# mainboard.net
KiCad netlist of a schematic drawn in EAGLE
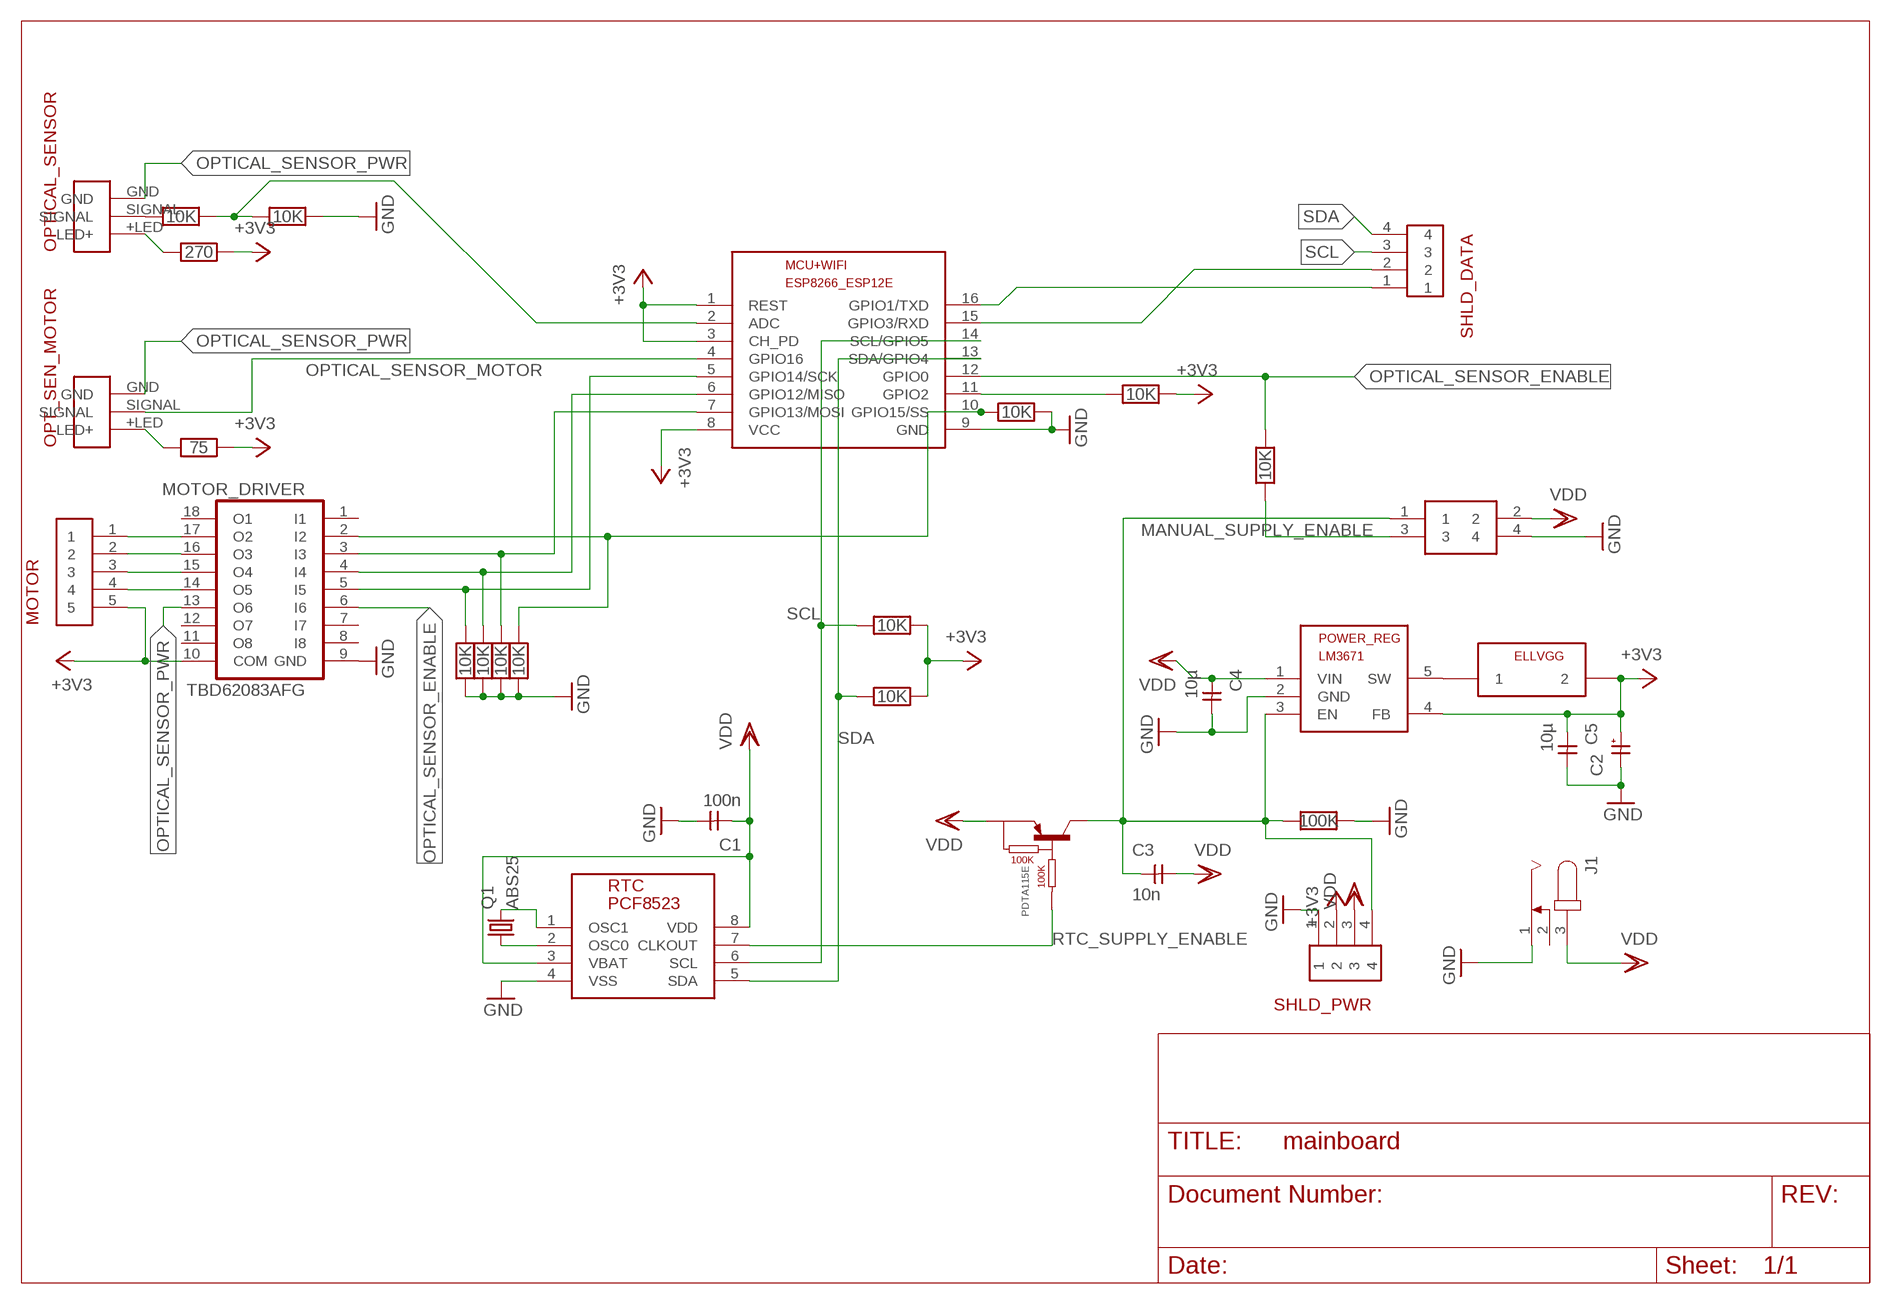
[diagram p0: schematic, sheet 1]

(export (version "E")
  (design (tool "Eeschema 10.0.6"))
  (components
    (comp (ref "C1")
      (value "100n")
      (footprint "eagle-import:SMD_RC_1206")
      (libsource (lib "eagle-import") (part "CSMD_1206"))
    )
    (comp (ref "C2")
      (value "C_POLSMD_M6.3")
      (footprint "eagle-import:C_M6.3")
      (libsource (lib "eagle-import") (part "C_POLSMD_M6.3"))
    )
    (comp (ref "C3")
      (value "10n")
      (footprint "eagle-import:SMD_RC_1206")
      (libsource (lib "eagle-import") (part "CSMD_1206"))
    )
    (comp (ref "C4")
      (value "10µ")
      (footprint "eagle-import:SMD_RC_1206")
      (libsource (lib "eagle-import") (part "CSMD_1206"))
    )
    (comp (ref "C5")
      (value "10µ")
      (footprint "eagle-import:SMD_RC_1206")
      (libsource (lib "eagle-import") (part "CSMD_1206"))
    )
    (comp (ref "DIL_SWITCH")
      (value "HEADER_2X2")
      (footprint "eagle-import:HEADER_2X2")
      (libsource (lib "eagle-import") (part "HEADER_2X2"))
    )
    (comp (ref "J1")
      (value "JACK-PLUG0")
      (footprint "eagle-import:SPC4077")
      (libsource (lib "eagle-import") (part "JACK-PLUG0"))
    )
    (comp (ref "L1")
      (value "ELLVGG")
      (footprint "eagle-import:ELLVGG")
      (libsource (lib "eagle-import") (part "ELLVGG"))
    )
    (comp (ref "MCU+WIFI")
      (value "ESP8266-12EESP8266-ESP12E")
      (footprint "eagle-import:ESP8266-ESP12E")
      (libsource (lib "eagle-import") (part "ESP8266-12EESP8266-ESP12E"))
    )
    (comp (ref "MOTOR")
      (value "B5B-XH-A")
      (footprint "eagle-import:B5B-XH-A")
      (libsource (lib "eagle-import") (part "B5B-XH-A"))
    )
    (comp (ref "MOTOR_DRIVER")
      (value "TBD62083AFG")
      (footprint "eagle-import:SO18")
      (libsource (lib "eagle-import") (part "TBD62083AFG"))
    )
    (comp (ref "OPTICAL_SENSOR")
      (value "ENDSTOP")
      (footprint "eagle-import:ENDSTOP")
      (libsource (lib "eagle-import") (part "ENDSTOP"))
    )
    (comp (ref "OPT_SEN_MOTOR")
      (value "ENDSTOP")
      (footprint "eagle-import:ENDSTOP")
      (libsource (lib "eagle-import") (part "ENDSTOP"))
    )
    (comp (ref "POWER_REG")
      (value "LM3671NO_EXTRA_PAD")
      (footprint "eagle-import:SOT23-5L-SIMPLE")
      (libsource (lib "eagle-import") (part "LM3671NO_EXTRA_PAD"))
    )
    (comp (ref "Q1")
      (value "ABS25")
      (footprint "eagle-import:ABS25")
      (libsource (lib "eagle-import") (part "ABS25"))
    )
    (comp (ref "R1")
      (value "270")
      (footprint "eagle-import:SMD_RC_1206")
      (libsource (lib "eagle-import") (part "RSMD_1206"))
    )
    (comp (ref "R2")
      (value "10K")
      (footprint "eagle-import:SMD_RC_1206")
      (libsource (lib "eagle-import") (part "RSMD_1206"))
    )
    (comp (ref "R3")
      (value "10K")
      (footprint "eagle-import:SMD_RC_1206")
      (libsource (lib "eagle-import") (part "RSMD_1206"))
    )
    (comp (ref "R4")
      (value "100K")
      (footprint "eagle-import:SMD_RC_1206")
      (libsource (lib "eagle-import") (part "RSMD_1206"))
    )
    (comp (ref "R5")
      (value "10K")
      (footprint "eagle-import:SMD_RC_1206")
      (libsource (lib "eagle-import") (part "RSMD_1206"))
    )
    (comp (ref "R6")
      (value "10K")
      (footprint "eagle-import:SMD_RC_1206")
      (libsource (lib "eagle-import") (part "RSMD_1206"))
    )
    (comp (ref "R7")
      (value "10K")
      (footprint "eagle-import:SMD_RC_1206")
      (libsource (lib "eagle-import") (part "RSMD_1206"))
    )
    (comp (ref "R8")
      (value "10K")
      (footprint "eagle-import:SMD_RC_1206")
      (libsource (lib "eagle-import") (part "RSMD_1206"))
    )
    (comp (ref "R9")
      (value "10K")
      (footprint "eagle-import:SMD_RC_1206")
      (libsource (lib "eagle-import") (part "RSMD_1206"))
    )
    (comp (ref "R10")
      (value "10K")
      (footprint "eagle-import:SMD_RC_1206")
      (libsource (lib "eagle-import") (part "RSMD_1206"))
    )
    (comp (ref "R11")
      (value "10K")
      (footprint "eagle-import:SMD_RC_1206")
      (libsource (lib "eagle-import") (part "RSMD_1206"))
    )
    (comp (ref "R12")
      (value "10K")
      (footprint "eagle-import:SMD_RC_1206")
      (libsource (lib "eagle-import") (part "RSMD_1206"))
    )
    (comp (ref "R13")
      (value "10K")
      (footprint "eagle-import:SMD_RC_1206")
      (libsource (lib "eagle-import") (part "RSMD_1206"))
    )
    (comp (ref "R14")
      (value "75")
      (footprint "eagle-import:SMD_RC_1206")
      (libsource (lib "eagle-import") (part "RSMD_1206"))
    )
    (comp (ref "RTC")
      (value "PCF8523TS")
      (footprint "eagle-import:SO8")
      (libsource (lib "eagle-import") (part "PCF8523TS"))
    )
    (comp (ref "SHLD_DATA")
      (value "HEADER_1X4")
      (footprint "eagle-import:HEADER_1X4")
      (libsource (lib "eagle-import") (part "HEADER_1X4"))
    )
    (comp (ref "SHLD_PWR")
      (value "HEADER_1X4")
      (footprint "eagle-import:HEADER_1X4")
      (libsource (lib "eagle-import") (part "HEADER_1X4"))
    )
    (comp (ref "T1")
      (value "PDTA115ET")
      (footprint "eagle-import:SOT23")
      (libsource (lib "eagle-import") (part "PDTA115ET"))
    )
  )
  (nets
    (net (code "1") (name "+3V3") (class "Default")
      (node (ref "C2") (pin "+") (pinfunction "+_+") (pintype "passive"))
      (node (ref "C5") (pin "P$1") (pinfunction "1_P$1") (pintype "passive"))
      (node (ref "L1") (pin "P$2") (pinfunction "2_P$2") (pintype "bidirectional"))
      (node (ref "MCU+WIFI") (pin "1") (pinfunction "REST_1") (pintype "bidirectional"))
      (node (ref "MCU+WIFI") (pin "3") (pinfunction "CH_PD_3") (pintype "bidirectional"))
      (node (ref "MCU+WIFI") (pin "8") (pinfunction "VCC_8") (pintype "bidirectional"))
      (node (ref "MOTOR") (pin "5") (pinfunction "5_5") (pintype "passive"))
      (node (ref "MOTOR_DRIVER") (pin "10") (pinfunction "COM_10") (pintype "passive"))
      (node (ref "POWER_REG") (pin "4") (pinfunction "FB_4") (pintype "bidirectional"))
      (node (ref "R1") (pin "P$2") (pinfunction "P$2_P$2") (pintype "passive"))
      (node (ref "R10") (pin "P$2") (pinfunction "P$2_P$2") (pintype "passive"))
      (node (ref "R11") (pin "P$2") (pinfunction "P$2_P$2") (pintype "passive"))
      (node (ref "R14") (pin "P$2") (pinfunction "P$2_P$2") (pintype "passive"))
      (node (ref "R9") (pin "P$2") (pinfunction "P$2_P$2") (pintype "passive"))
      (node (ref "SHLD_PWR") (pin "2") (pinfunction "2_2") (pintype "passive"))
    )
    (net (code "2") (name "/MANUAL_SUPPLY_ENABLE") (class "Default")
      (node (ref "C3") (pin "P$1") (pinfunction "1_P$1") (pintype "passive"))
      (node (ref "DIL_SWITCH") (pin "1") (pinfunction "1_1") (pintype "bidirectional"))
      (node (ref "POWER_REG") (pin "3") (pinfunction "EN_3") (pintype "bidirectional"))
      (node (ref "R4") (pin "P$2") (pinfunction "P$2_P$2") (pintype "passive"))
      (node (ref "SHLD_PWR") (pin "4") (pinfunction "4_4") (pintype "passive"))
      (node (ref "T1") (pin "3") (pinfunction "C_3") (pintype "passive"))
    )
    (net (code "3") (name "/OPTICAL_SENSOR_MOTOR") (class "Default")
      (node (ref "MCU+WIFI") (pin "4") (pinfunction "GPIO16_4") (pintype "bidirectional"))
      (node (ref "OPT_SEN_MOTOR") (pin "SIGNAL") (pinfunction "SIGNAL_SIGNAL") (pintype "passive"))
    )
    (net (code "4") (name "/RTC_SUPPLY_ENABLE") (class "Default")
      (node (ref "RTC") (pin "7") (pinfunction "CLKOUT_7") (pintype "output"))
      (node (ref "T1") (pin "1") (pinfunction "B_1") (pintype "passive"))
    )
    (net (code "5") (name "GND") (class "Default")
      (node (ref "C1") (pin "P$2") (pinfunction "2_P$2") (pintype "passive"))
      (node (ref "C2") (pin "GND") (pinfunction "GND_GND") (pintype "passive"))
      (node (ref "C4") (pin "P$2") (pinfunction "2_P$2") (pintype "passive"))
      (node (ref "C5") (pin "P$2") (pinfunction "2_P$2") (pintype "passive"))
      (node (ref "DIL_SWITCH") (pin "4") (pinfunction "4_4") (pintype "bidirectional"))
      (node (ref "J1") (pin "1") (pinfunction "1_1") (pintype "passive"))
      (node (ref "MCU+WIFI") (pin "9") (pinfunction "GND_9") (pintype "bidirectional"))
      (node (ref "MOTOR_DRIVER") (pin "9") (pinfunction "GND_9") (pintype "power_in"))
      (node (ref "POWER_REG") (pin "2") (pinfunction "GND_2") (pintype "bidirectional"))
      (node (ref "R12") (pin "P$1") (pinfunction "P$1_P$1") (pintype "passive"))
      (node (ref "R13") (pin "P$1") (pinfunction "P$1_P$1") (pintype "passive"))
      (node (ref "R3") (pin "P$2") (pinfunction "P$2_P$2") (pintype "passive"))
      (node (ref "R4") (pin "P$1") (pinfunction "P$1_P$1") (pintype "passive"))
      (node (ref "R5") (pin "P$1") (pinfunction "P$1_P$1") (pintype "passive"))
      (node (ref "R6") (pin "P$1") (pinfunction "P$1_P$1") (pintype "passive"))
      (node (ref "R7") (pin "P$2") (pinfunction "P$2_P$2") (pintype "passive"))
      (node (ref "RTC") (pin "4") (pinfunction "VSS_4") (pintype "power_in"))
      (node (ref "SHLD_PWR") (pin "1") (pinfunction "1_1") (pintype "passive"))
    )
    (net (code "6") (name "Net-(DIL_SWITCH-Pad3)") (class "Default")
      (node (ref "DIL_SWITCH") (pin "3") (pinfunction "3_3") (pintype "bidirectional"))
      (node (ref "R8") (pin "P$2") (pinfunction "P$2_P$2") (pintype "passive"))
    )
    (net (code "7") (name "Net-(L1-1)") (class "Default")
      (node (ref "L1") (pin "P$1") (pinfunction "1_P$1") (pintype "bidirectional"))
      (node (ref "POWER_REG") (pin "5") (pinfunction "SW_5") (pintype "bidirectional"))
    )
    (net (code "8") (name "Net-(MCU+WIFI-ADC)") (class "Default")
      (node (ref "MCU+WIFI") (pin "2") (pinfunction "ADC_2") (pintype "bidirectional"))
      (node (ref "R2") (pin "P$2") (pinfunction "P$2_P$2") (pintype "passive"))
      (node (ref "R3") (pin "P$1") (pinfunction "P$1_P$1") (pintype "passive"))
    )
    (net (code "9") (name "Net-(MCU+WIFI-GPIO1{slash}TXD)") (class "Default")
      (node (ref "MCU+WIFI") (pin "16") (pinfunction "GPIO1/TXD_16") (pintype "bidirectional"))
      (node (ref "SHLD_DATA") (pin "1") (pinfunction "1_1") (pintype "passive"))
    )
    (net (code "10") (name "Net-(MCU+WIFI-GPIO2)") (class "Default")
      (node (ref "MCU+WIFI") (pin "11") (pinfunction "GPIO2_11") (pintype "bidirectional"))
      (node (ref "R11") (pin "P$1") (pinfunction "P$1_P$1") (pintype "passive"))
    )
    (net (code "11") (name "Net-(MCU+WIFI-GPIO3{slash}RXD)") (class "Default")
      (node (ref "MCU+WIFI") (pin "15") (pinfunction "GPIO3/RXD_15") (pintype "bidirectional"))
      (node (ref "SHLD_DATA") (pin "2") (pinfunction "2_2") (pintype "passive"))
    )
    (net (code "12") (name "Net-(MCU+WIFI-GPIO12{slash}MISO)") (class "Default")
      (node (ref "MCU+WIFI") (pin "6") (pinfunction "GPIO12/MISO_6") (pintype "bidirectional"))
      (node (ref "MOTOR_DRIVER") (pin "4") (pinfunction "I4_4") (pintype "input"))
      (node (ref "R6") (pin "P$2") (pinfunction "P$2_P$2") (pintype "passive"))
    )
    (net (code "13") (name "Net-(MCU+WIFI-GPIO13{slash}MOSI)") (class "Default")
      (node (ref "MCU+WIFI") (pin "7") (pinfunction "GPIO13/MOSI_7") (pintype "bidirectional"))
      (node (ref "MOTOR_DRIVER") (pin "3") (pinfunction "I3_3") (pintype "input"))
      (node (ref "R12") (pin "P$2") (pinfunction "P$2_P$2") (pintype "passive"))
    )
    (net (code "14") (name "Net-(MCU+WIFI-GPIO14{slash}SCK)") (class "Default")
      (node (ref "MCU+WIFI") (pin "5") (pinfunction "GPIO14/SCK_5") (pintype "bidirectional"))
      (node (ref "MOTOR_DRIVER") (pin "5") (pinfunction "I5_5") (pintype "input"))
      (node (ref "R5") (pin "P$2") (pinfunction "P$2_P$2") (pintype "passive"))
    )
    (net (code "15") (name "Net-(MCU+WIFI-GPIO15{slash}SS)") (class "Default")
      (node (ref "MCU+WIFI") (pin "10") (pinfunction "GPIO15/SS_10") (pintype "bidirectional"))
      (node (ref "MOTOR_DRIVER") (pin "2") (pinfunction "I2_2") (pintype "input"))
      (node (ref "R13") (pin "P$2") (pinfunction "P$2_P$2") (pintype "passive"))
      (node (ref "R7") (pin "P$1") (pinfunction "P$1_P$1") (pintype "passive"))
    )
    (net (code "16") (name "Net-(MOTOR_DRIVER-O2)") (class "Default")
      (node (ref "MOTOR") (pin "1") (pinfunction "1_1") (pintype "passive"))
      (node (ref "MOTOR_DRIVER") (pin "17") (pinfunction "O2_17") (pintype "open_collector"))
    )
    (net (code "17") (name "Net-(MOTOR_DRIVER-O3)") (class "Default")
      (node (ref "MOTOR") (pin "2") (pinfunction "2_2") (pintype "passive"))
      (node (ref "MOTOR_DRIVER") (pin "16") (pinfunction "O3_16") (pintype "open_collector"))
    )
    (net (code "18") (name "Net-(MOTOR_DRIVER-O4)") (class "Default")
      (node (ref "MOTOR") (pin "3") (pinfunction "3_3") (pintype "passive"))
      (node (ref "MOTOR_DRIVER") (pin "15") (pinfunction "O4_15") (pintype "open_collector"))
    )
    (net (code "19") (name "Net-(MOTOR_DRIVER-O5)") (class "Default")
      (node (ref "MOTOR") (pin "4") (pinfunction "4_4") (pintype "passive"))
      (node (ref "MOTOR_DRIVER") (pin "14") (pinfunction "O5_14") (pintype "open_collector"))
    )
    (net (code "20") (name "Net-(OPTICAL_SENSOR-LED+)") (class "Default")
      (node (ref "OPTICAL_SENSOR") (pin "+LED") (pinfunction "LED+_+LED") (pintype "passive"))
      (node (ref "R1") (pin "P$1") (pinfunction "P$1_P$1") (pintype "passive"))
    )
    (net (code "21") (name "Net-(OPTICAL_SENSOR-PadSIGNAL)") (class "Default")
      (node (ref "OPTICAL_SENSOR") (pin "SIGNAL") (pinfunction "SIGNAL_SIGNAL") (pintype "passive"))
      (node (ref "R2") (pin "P$1") (pinfunction "P$1_P$1") (pintype "passive"))
    )
    (net (code "22") (name "Net-(OPT_SEN_MOTOR-LED+)") (class "Default")
      (node (ref "OPT_SEN_MOTOR") (pin "+LED") (pinfunction "LED+_+LED") (pintype "passive"))
      (node (ref "R14") (pin "P$1") (pinfunction "P$1_P$1") (pintype "passive"))
    )
    (net (code "23") (name "Net-(Q1-2)") (class "Default")
      (node (ref "Q1") (pin "4") (pinfunction "2_4") (pintype "passive"))
      (node (ref "RTC") (pin "1") (pinfunction "OSC1_1") (pintype "bidirectional"))
    )
    (net (code "24") (name "Net-(RTC-OSC0)") (class "Default")
      (node (ref "Q1") (pin "1") (pinfunction "1_1") (pintype "passive"))
      (node (ref "RTC") (pin "2") (pinfunction "OSC0_2") (pintype "bidirectional"))
    )
    (net (code "25") (name "OPTICAL_SENSOR_ENABLE") (class "Default")
      (node (ref "MCU+WIFI") (pin "12") (pinfunction "GPIO0_12") (pintype "bidirectional"))
      (node (ref "MOTOR_DRIVER") (pin "6") (pinfunction "I6_6") (pintype "input"))
      (node (ref "R8") (pin "P$1") (pinfunction "P$1_P$1") (pintype "passive"))
    )
    (net (code "26") (name "OPTICAL_SENSOR_PWR") (class "Default")
      (node (ref "MOTOR_DRIVER") (pin "13") (pinfunction "O6_13") (pintype "open_collector"))
      (node (ref "OPTICAL_SENSOR") (pin "GND") (pinfunction "GND_GND") (pintype "passive"))
      (node (ref "OPT_SEN_MOTOR") (pin "GND") (pinfunction "GND_GND") (pintype "passive"))
    )
    (net (code "27") (name "SCL") (class "Default")
      (node (ref "MCU+WIFI") (pin "14") (pinfunction "SCL/GPIO5_14") (pintype "bidirectional"))
      (node (ref "R9") (pin "P$1") (pinfunction "P$1_P$1") (pintype "passive"))
      (node (ref "RTC") (pin "6") (pinfunction "SCL_6") (pintype "input"))
      (node (ref "SHLD_DATA") (pin "3") (pinfunction "3_3") (pintype "passive"))
    )
    (net (code "28") (name "SDA") (class "Default")
      (node (ref "MCU+WIFI") (pin "13") (pinfunction "SDA/GPIO4_13") (pintype "bidirectional"))
      (node (ref "R10") (pin "P$1") (pinfunction "P$1_P$1") (pintype "passive"))
      (node (ref "RTC") (pin "5") (pinfunction "SDA_5") (pintype "bidirectional"))
      (node (ref "SHLD_DATA") (pin "4") (pinfunction "4_4") (pintype "passive"))
    )
    (net (code "29") (name "VDD") (class "Default")
      (node (ref "C1") (pin "P$1") (pinfunction "1_P$1") (pintype "passive"))
      (node (ref "C3") (pin "P$2") (pinfunction "2_P$2") (pintype "passive"))
      (node (ref "C4") (pin "P$1") (pinfunction "1_P$1") (pintype "passive"))
      (node (ref "DIL_SWITCH") (pin "2") (pinfunction "2_2") (pintype "bidirectional"))
      (node (ref "J1") (pin "3") (pinfunction "3_3") (pintype "passive"))
      (node (ref "POWER_REG") (pin "1") (pinfunction "VIN_1") (pintype "bidirectional"))
      (node (ref "RTC") (pin "3") (pinfunction "VBAT_3") (pintype "power_in"))
      (node (ref "RTC") (pin "8") (pinfunction "VDD_8") (pintype "power_in"))
      (node (ref "SHLD_PWR") (pin "3") (pinfunction "3_3") (pintype "passive"))
      (node (ref "T1") (pin "2") (pinfunction "E_2") (pintype "passive"))
    )
    (net (code "30") (name "unconnected-(J1-Pad2)") (class "Default")
      (node (ref "J1") (pin "2") (pinfunction "2_2") (pintype "passive"))
    )
    (net (code "31") (name "unconnected-(MOTOR_DRIVER-I1-Pad1)") (class "Default")
      (node (ref "MOTOR_DRIVER") (pin "1") (pinfunction "I1_1") (pintype "input"))
    )
    (net (code "32") (name "unconnected-(MOTOR_DRIVER-I7-Pad7)") (class "Default")
      (node (ref "MOTOR_DRIVER") (pin "7") (pinfunction "I7_7") (pintype "input"))
    )
    (net (code "33") (name "unconnected-(MOTOR_DRIVER-I8-Pad8)") (class "Default")
      (node (ref "MOTOR_DRIVER") (pin "8") (pinfunction "I8_8") (pintype "input"))
    )
    (net (code "34") (name "unconnected-(MOTOR_DRIVER-O1-Pad18)") (class "Default")
      (node (ref "MOTOR_DRIVER") (pin "18") (pinfunction "O1_18") (pintype "open_collector"))
    )
    (net (code "35") (name "unconnected-(MOTOR_DRIVER-O7-Pad12)") (class "Default")
      (node (ref "MOTOR_DRIVER") (pin "12") (pinfunction "O7_12") (pintype "open_collector"))
    )
    (net (code "36") (name "unconnected-(MOTOR_DRIVER-O8-Pad11)") (class "Default")
      (node (ref "MOTOR_DRIVER") (pin "11") (pinfunction "O8_11") (pintype "open_collector"))
    )
  )
)
